# univ_3-2-3-x-rev2.net
KiCad netlist of a schematic drawn in EAGLE
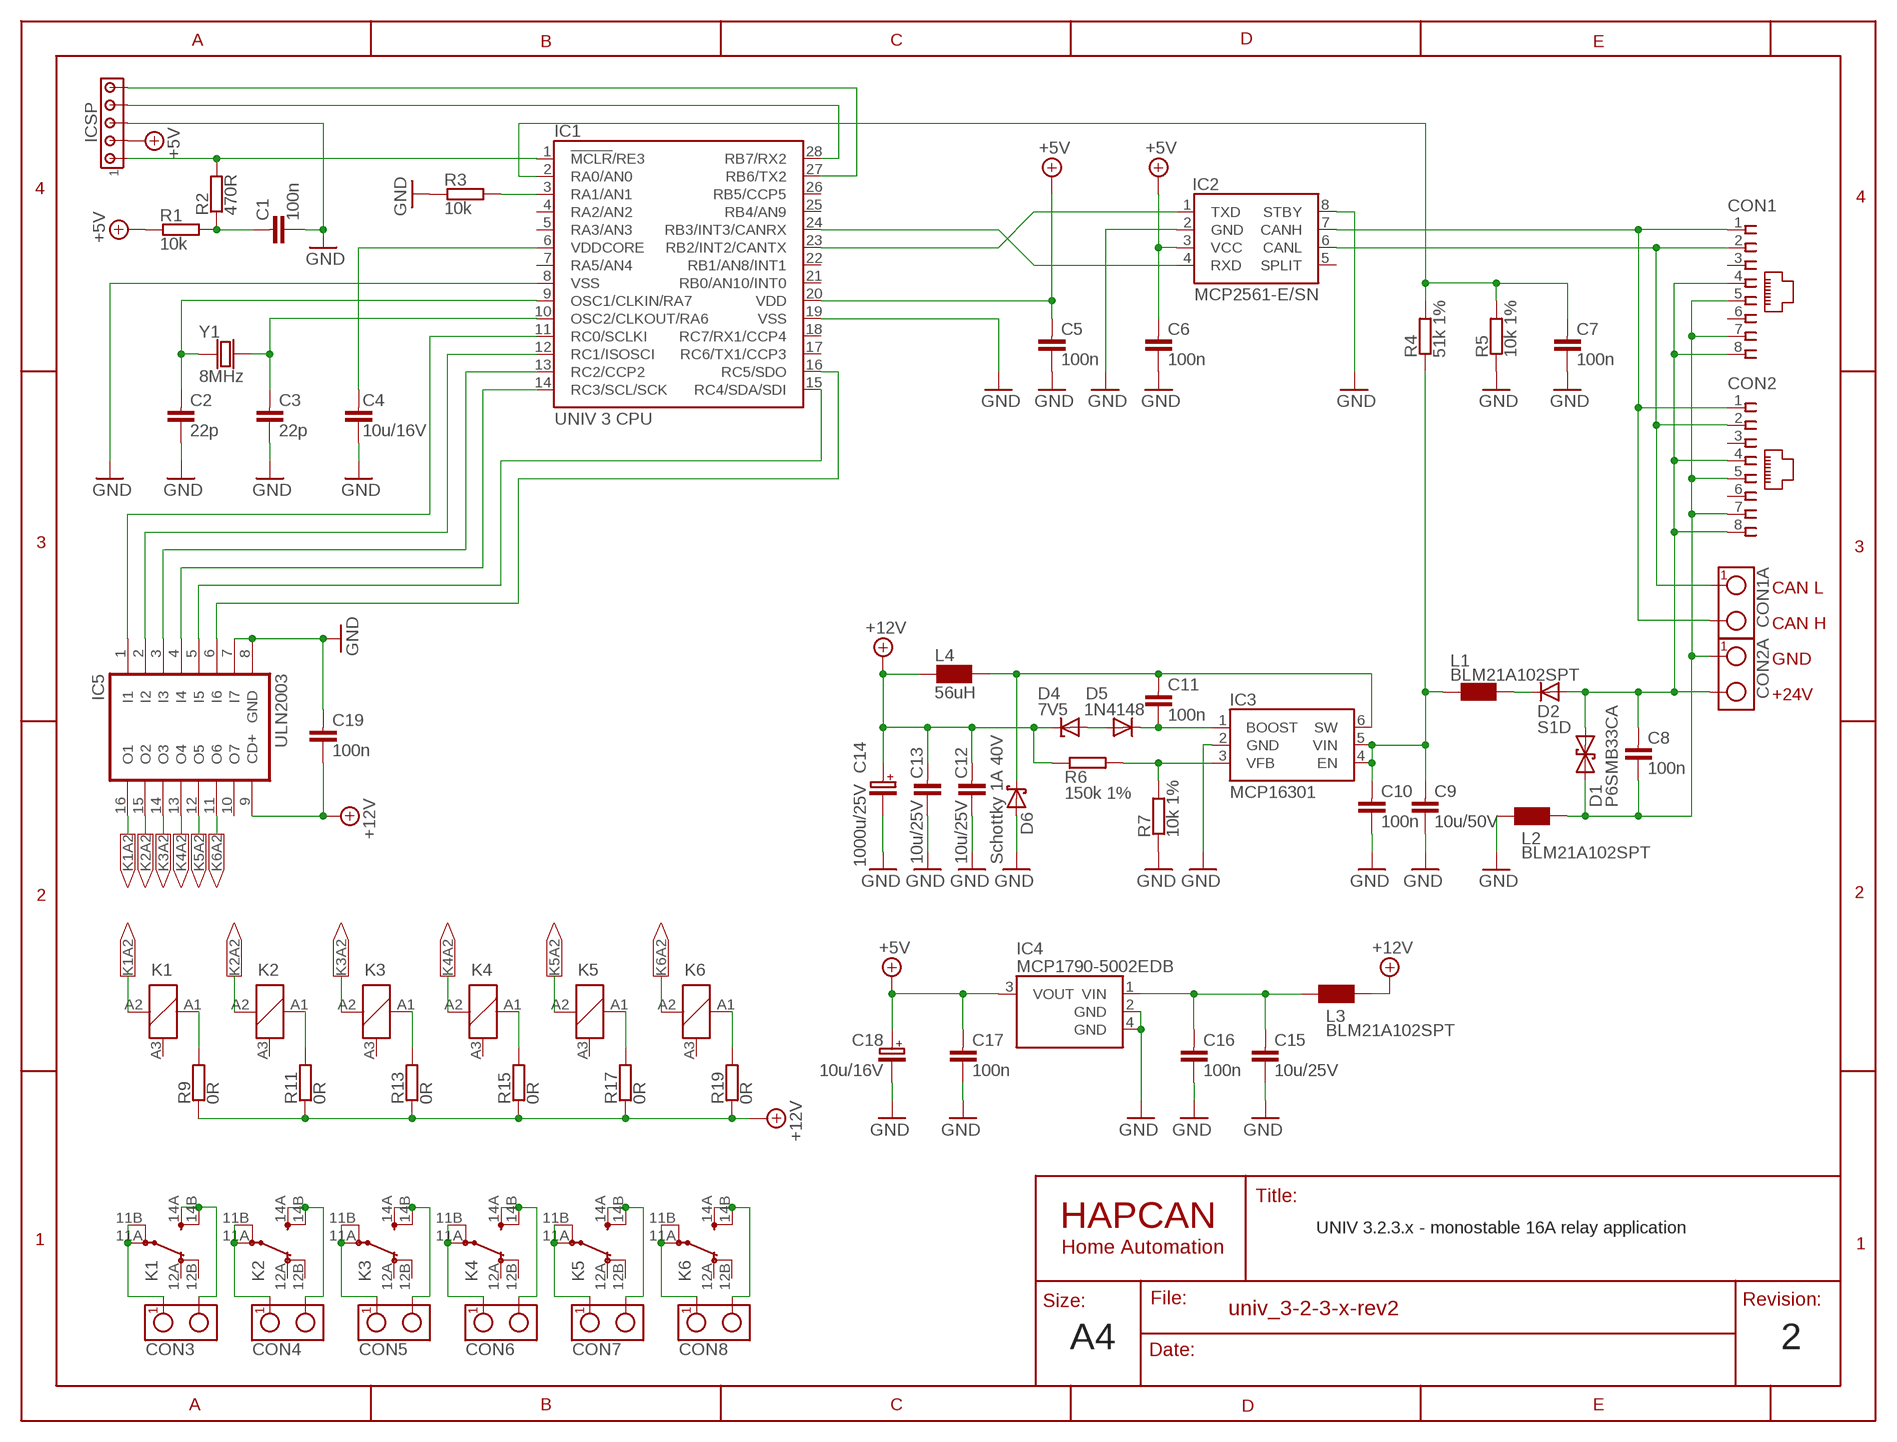
[diagram p0: schematic, sheet 1]

(export (version "E")
  (design (tool "Eeschema 10.0.6"))
  (components
    (comp (ref "C1")
      (value "100n")
      (footprint "eagle-import:0805")
      (libsource (lib "eagle-import") (part "CAPACITOR0805"))
    )
    (comp (ref "C2")
      (value "22p")
      (footprint "eagle-import:0805")
      (libsource (lib "eagle-import") (part "CAPACITOR0805"))
    )
    (comp (ref "C3")
      (value "22p")
      (footprint "eagle-import:0805")
      (libsource (lib "eagle-import") (part "CAPACITOR0805"))
    )
    (comp (ref "C4")
      (value "10u/16V")
      (footprint "eagle-import:0805")
      (libsource (lib "eagle-import") (part "CAPACITOR0805"))
    )
    (comp (ref "C5")
      (value "100n")
      (footprint "eagle-import:0805")
      (libsource (lib "eagle-import") (part "CAPACITOR0805"))
    )
    (comp (ref "C6")
      (value "100n")
      (footprint "eagle-import:0805")
      (libsource (lib "eagle-import") (part "CAPACITOR0805"))
    )
    (comp (ref "C7")
      (value "100n")
      (footprint "eagle-import:0805")
      (libsource (lib "eagle-import") (part "CAPACITOR0805"))
    )
    (comp (ref "C8")
      (value "100n")
      (footprint "eagle-import:0805")
      (libsource (lib "eagle-import") (part "CAPACITOR0805"))
    )
    (comp (ref "C9")
      (value "10u/50V")
      (footprint "eagle-import:1210")
      (libsource (lib "eagle-import") (part "CAPACITOR1210"))
    )
    (comp (ref "C10")
      (value "100n")
      (footprint "eagle-import:0805")
      (libsource (lib "eagle-import") (part "CAPACITOR0805"))
    )
    (comp (ref "C11")
      (value "100n")
      (footprint "eagle-import:0805")
      (libsource (lib "eagle-import") (part "CAPACITOR0805"))
    )
    (comp (ref "C12")
      (value "10u/25V")
      (footprint "eagle-import:1206")
      (libsource (lib "eagle-import") (part "CAPACITOR1206"))
    )
    (comp (ref "C13")
      (value "10u/25V")
      (footprint "eagle-import:1206")
      (libsource (lib "eagle-import") (part "CAPACITOR1206"))
    )
    (comp (ref "C14")
      (value "1000u/25V")
      (footprint "eagle-import:CAP-5X10.5")
      (libsource (lib "eagle-import") (part "CAPACITOR-POLARIZED-5X10.5"))
    )
    (comp (ref "C15")
      (value "10u/25V")
      (footprint "eagle-import:1206")
      (libsource (lib "eagle-import") (part "CAPACITOR1206"))
    )
    (comp (ref "C16")
      (value "100n")
      (footprint "eagle-import:0805")
      (libsource (lib "eagle-import") (part "CAPACITOR0805"))
    )
    (comp (ref "C17")
      (value "100n")
      (footprint "eagle-import:0805")
      (libsource (lib "eagle-import") (part "CAPACITOR0805"))
    )
    (comp (ref "C18")
      (value "10u/16V")
      (footprint "eagle-import:SMC_B")
      (libsource (lib "eagle-import") (part "CAPACITOR-POLARIZED-SMC_B"))
    )
    (comp (ref "C19")
      (value "100n")
      (footprint "eagle-import:0805")
      (libsource (lib "eagle-import") (part "CAPACITOR0805"))
    )
    (comp (ref "CON1")
      (value "RJ45-SOCKET")
      (footprint "eagle-import:RJ45-PCB-SOCKET")
      (libsource (lib "eagle-import") (part "RJ45-SOCKET"))
    )
    (comp (ref "CON1A")
      (value "TERMINAL-2")
      (footprint "eagle-import:ARK2-5X10,5MM")
      (libsource (lib "eagle-import") (part "TERMINAL-2-5X10,5MM"))
    )
    (comp (ref "CON2")
      (value "RJ45-SOCKET")
      (footprint "eagle-import:RJ45-PCB-SOCKET")
      (libsource (lib "eagle-import") (part "RJ45-SOCKET"))
    )
    (comp (ref "CON2A")
      (value "TERMINAL-2")
      (footprint "eagle-import:ARK2-5X10,5MM")
      (libsource (lib "eagle-import") (part "TERMINAL-2-5X10,5MM"))
    )
    (comp (ref "CON3")
      (value "TERMINAL-2")
      (footprint "eagle-import:ARK2-7.5X10.5MM")
      (libsource (lib "eagle-import") (part "TERMINAL-2-7.5X10.5MM"))
    )
    (comp (ref "CON4")
      (value "TERMINAL-2")
      (footprint "eagle-import:ARK2-7.5X10.5MM")
      (libsource (lib "eagle-import") (part "TERMINAL-2-7.5X10.5MM"))
    )
    (comp (ref "CON5")
      (value "TERMINAL-2")
      (footprint "eagle-import:ARK2-7.5X10.5MM")
      (libsource (lib "eagle-import") (part "TERMINAL-2-7.5X10.5MM"))
    )
    (comp (ref "CON6")
      (value "TERMINAL-2")
      (footprint "eagle-import:ARK2-7.5X10.5MM")
      (libsource (lib "eagle-import") (part "TERMINAL-2-7.5X10.5MM"))
    )
    (comp (ref "CON7")
      (value "TERMINAL-2")
      (footprint "eagle-import:ARK2-7.5X10.5MM")
      (libsource (lib "eagle-import") (part "TERMINAL-2-7.5X10.5MM"))
    )
    (comp (ref "CON8")
      (value "TERMINAL-2")
      (footprint "eagle-import:ARK2-7.5X10.5MM")
      (libsource (lib "eagle-import") (part "TERMINAL-2-7.5X10.5MM"))
    )
    (comp (ref "D1")
      (value "P6SMB33CA")
      (footprint "eagle-import:DO-214_TRANSIL2")
      (libsource (lib "eagle-import") (part "DIODE_TRANSIL2"))
    )
    (comp (ref "D2")
      (value "S1D")
      (footprint "eagle-import:DO-214")
      (libsource (lib "eagle-import") (part "DIODE_DO-214"))
    )
    (comp (ref "D4")
      (value "7V5")
      (footprint "eagle-import:SOD-80")
      (libsource (lib "eagle-import") (part "DIODE_ZENER_SOD-80"))
    )
    (comp (ref "D5")
      (value "1N4148")
      (footprint "eagle-import:0805")
      (libsource (lib "eagle-import") (part "DIODE_0805"))
    )
    (comp (ref "D6")
      (value "Schottky 1A 40V")
      (footprint "eagle-import:DO-214")
      (libsource (lib "eagle-import") (part "DIODE_TRANSIL1_DO214"))
    )
    (comp (ref "IC1")
      (value "UNIV 3 CPU")
      (footprint "eagle-import:UNIV3CPU")
      (libsource (lib "eagle-import") (part "UNIV3CPU-I/SO"))
    )
    (comp (ref "IC2")
      (value "MCP2561-E/SN")
      (footprint "eagle-import:SO-08")
      (libsource (lib "eagle-import") (part "MCP2561-E/SN"))
    )
    (comp (ref "IC3")
      (value "MCP16301")
      (footprint "eagle-import:SOT-23-6")
      (libsource (lib "eagle-import") (part "MCP16301SOT23-6"))
    )
    (comp (ref "IC4")
      (value "MCP1790-5002EDB")
      (footprint "eagle-import:SOT-223")
      (libsource (lib "eagle-import") (part "MCP1826SOT223-3"))
    )
    (comp (ref "IC5")
      (value "ULN2003")
      (footprint "eagle-import:SO-16")
      (libsource (lib "eagle-import") (part "ULN2003"))
    )
    (comp (ref "ICSP")
      (value "HEADER5")
      (footprint "eagle-import:SIP-5")
      (libsource (lib "eagle-import") (part "HEADER5"))
    )
    (comp (ref "K1")
      (value "RELAY_RT")
      (footprint "eagle-import:RELAY_RT")
      (libsource (lib "eagle-import") (part "RELAY_RT"))
    )
    (comp (ref "K2")
      (value "RELAY_RT")
      (footprint "eagle-import:RELAY_RT")
      (libsource (lib "eagle-import") (part "RELAY_RT"))
    )
    (comp (ref "K3")
      (value "RELAY_RT")
      (footprint "eagle-import:RELAY_RT")
      (libsource (lib "eagle-import") (part "RELAY_RT"))
    )
    (comp (ref "K4")
      (value "RELAY_RT")
      (footprint "eagle-import:RELAY_RT")
      (libsource (lib "eagle-import") (part "RELAY_RT"))
    )
    (comp (ref "K5")
      (value "RELAY_RT")
      (footprint "eagle-import:RELAY_RT")
      (libsource (lib "eagle-import") (part "RELAY_RT"))
    )
    (comp (ref "K6")
      (value "RELAY_RT")
      (footprint "eagle-import:RELAY_RT")
      (libsource (lib "eagle-import") (part "RELAY_RT"))
    )
    (comp (ref "L1")
      (value "BLM21A102SPT")
      (footprint "eagle-import:0805")
      (libsource (lib "eagle-import") (part "CHOKE0805"))
    )
    (comp (ref "L2")
      (value "BLM21A102SPT")
      (footprint "eagle-import:0805")
      (libsource (lib "eagle-import") (part "CHOKE0805"))
    )
    (comp (ref "L3")
      (value "BLM21A102SPT")
      (footprint "eagle-import:0805")
      (libsource (lib "eagle-import") (part "CHOKE0805"))
    )
    (comp (ref "L4")
      (value "56uH")
      (footprint "eagle-import:CHOKE-DER0705")
      (libsource (lib "eagle-import") (part "CHOKEDER0705"))
    )
    (comp (ref "R1")
      (value "10k")
      (footprint "eagle-import:0805")
      (libsource (lib "eagle-import") (part "RESISTOR0805"))
    )
    (comp (ref "R2")
      (value "470R")
      (footprint "eagle-import:0805")
      (libsource (lib "eagle-import") (part "RESISTOR0805"))
    )
    (comp (ref "R3")
      (value "10k")
      (footprint "eagle-import:0805")
      (libsource (lib "eagle-import") (part "RESISTOR0805"))
    )
    (comp (ref "R4")
      (value "51k 1%")
      (footprint "eagle-import:0805")
      (libsource (lib "eagle-import") (part "RESISTOR0805"))
    )
    (comp (ref "R5")
      (value "10k 1%")
      (footprint "eagle-import:0805")
      (libsource (lib "eagle-import") (part "RESISTOR0805"))
    )
    (comp (ref "R6")
      (value "150k 1%")
      (footprint "eagle-import:0805")
      (libsource (lib "eagle-import") (part "RESISTOR0805"))
    )
    (comp (ref "R7")
      (value "10k 1%")
      (footprint "eagle-import:0805")
      (libsource (lib "eagle-import") (part "RESISTOR0805"))
    )
    (comp (ref "R9")
      (value "0R")
      (footprint "eagle-import:1206")
      (libsource (lib "eagle-import") (part "RESISTOR1206"))
    )
    (comp (ref "R11")
      (value "0R")
      (footprint "eagle-import:1206")
      (libsource (lib "eagle-import") (part "RESISTOR1206"))
    )
    (comp (ref "R13")
      (value "0R")
      (footprint "eagle-import:1206")
      (libsource (lib "eagle-import") (part "RESISTOR1206"))
    )
    (comp (ref "R15")
      (value "0R")
      (footprint "eagle-import:1206")
      (libsource (lib "eagle-import") (part "RESISTOR1206"))
    )
    (comp (ref "R17")
      (value "0R")
      (footprint "eagle-import:1206")
      (libsource (lib "eagle-import") (part "RESISTOR1206"))
    )
    (comp (ref "R19")
      (value "0R")
      (footprint "eagle-import:1206")
      (libsource (lib "eagle-import") (part "RESISTOR1206"))
    )
    (comp (ref "Y1")
      (value "8MHz")
      (footprint "eagle-import:CRYSTAL-HC49V")
      (libsource (lib "eagle-import") (part "CRYSTAL-HC49V"))
    )
  )
  (nets
    (net (code "1") (name "+5V") (class "Default")
      (node (ref "C17") (pin "1") (pinfunction "1_1") (pintype "passive"))
      (node (ref "C18") (pin "+") (pinfunction "1_+") (pintype "passive"))
      (node (ref "C5") (pin "1") (pinfunction "1_1") (pintype "passive"))
      (node (ref "C6") (pin "1") (pinfunction "1_1") (pintype "passive"))
      (node (ref "IC1") (pin "20") (pinfunction "VDD_20") (pintype "bidirectional"))
      (node (ref "IC2") (pin "3") (pinfunction "VCC_3") (pintype "bidirectional"))
      (node (ref "IC4") (pin "3") (pinfunction "VOUT_3") (pintype "bidirectional"))
      (node (ref "ICSP") (pin "2") (pinfunction "2_2") (pintype "passive"))
      (node (ref "R1") (pin "1") (pinfunction "1_1") (pintype "passive"))
    )
    (net (code "2") (name "+12V") (class "Default")
      (node (ref "C12") (pin "1") (pinfunction "1_1") (pintype "passive"))
      (node (ref "C13") (pin "1") (pinfunction "1_1") (pintype "passive"))
      (node (ref "C14") (pin "+") (pinfunction "1_+") (pintype "passive"))
      (node (ref "C19") (pin "2") (pinfunction "2_2") (pintype "passive"))
      (node (ref "D4") (pin "C") (pinfunction "C_C") (pintype "passive"))
      (node (ref "IC5") (pin "9") (pinfunction "CD+_9") (pintype "passive"))
      (node (ref "L3") (pin "2") (pinfunction "2_2") (pintype "passive"))
      (node (ref "L4") (pin "1") (pinfunction "1_1") (pintype "passive"))
      (node (ref "R11") (pin "1") (pinfunction "1_1") (pintype "passive"))
      (node (ref "R13") (pin "1") (pinfunction "1_1") (pintype "passive"))
      (node (ref "R15") (pin "1") (pinfunction "1_1") (pintype "passive"))
      (node (ref "R17") (pin "1") (pinfunction "1_1") (pintype "passive"))
      (node (ref "R19") (pin "1") (pinfunction "1_1") (pintype "passive"))
      (node (ref "R6") (pin "1") (pinfunction "1_1") (pintype "passive"))
      (node (ref "R9") (pin "1") (pinfunction "1_1") (pintype "passive"))
    )
    (net (code "3") (name "/K1A2") (class "Default")
      (node (ref "IC5") (pin "16") (pinfunction "O1_16") (pintype "open_collector"))
      (node (ref "K1") (pin "A2") (pinfunction "R+_A2") (pintype "passive"))
    )
    (net (code "4") (name "/K2A2") (class "Default")
      (node (ref "IC5") (pin "15") (pinfunction "O2_15") (pintype "open_collector"))
      (node (ref "K2") (pin "A2") (pinfunction "R+_A2") (pintype "passive"))
    )
    (net (code "5") (name "/K3A2") (class "Default")
      (node (ref "IC5") (pin "14") (pinfunction "O3_14") (pintype "open_collector"))
      (node (ref "K3") (pin "A2") (pinfunction "R+_A2") (pintype "passive"))
    )
    (net (code "6") (name "/K4A2") (class "Default")
      (node (ref "IC5") (pin "13") (pinfunction "O4_13") (pintype "open_collector"))
      (node (ref "K4") (pin "A2") (pinfunction "R+_A2") (pintype "passive"))
    )
    (net (code "7") (name "/K5A2") (class "Default")
      (node (ref "IC5") (pin "12") (pinfunction "O5_12") (pintype "open_collector"))
      (node (ref "K5") (pin "A2") (pinfunction "R+_A2") (pintype "passive"))
    )
    (net (code "8") (name "/K6A2") (class "Default")
      (node (ref "IC5") (pin "11") (pinfunction "O6_11") (pintype "open_collector"))
      (node (ref "K6") (pin "A2") (pinfunction "R+_A2") (pintype "passive"))
    )
    (net (code "9") (name "GND") (class "Default")
      (node (ref "C1") (pin "2") (pinfunction "2_2") (pintype "passive"))
      (node (ref "C10") (pin "2") (pinfunction "2_2") (pintype "passive"))
      (node (ref "C12") (pin "2") (pinfunction "2_2") (pintype "passive"))
      (node (ref "C13") (pin "2") (pinfunction "2_2") (pintype "passive"))
      (node (ref "C14") (pin "-") (pinfunction "2_-") (pintype "passive"))
      (node (ref "C15") (pin "2") (pinfunction "2_2") (pintype "passive"))
      (node (ref "C16") (pin "2") (pinfunction "2_2") (pintype "passive"))
      (node (ref "C17") (pin "2") (pinfunction "2_2") (pintype "passive"))
      (node (ref "C18") (pin "-") (pinfunction "2_-") (pintype "passive"))
      (node (ref "C19") (pin "1") (pinfunction "1_1") (pintype "passive"))
      (node (ref "C2") (pin "2") (pinfunction "2_2") (pintype "passive"))
      (node (ref "C3") (pin "2") (pinfunction "2_2") (pintype "passive"))
      (node (ref "C4") (pin "2") (pinfunction "2_2") (pintype "passive"))
      (node (ref "C5") (pin "2") (pinfunction "2_2") (pintype "passive"))
      (node (ref "C6") (pin "2") (pinfunction "2_2") (pintype "passive"))
      (node (ref "C7") (pin "2") (pinfunction "2_2") (pintype "passive"))
      (node (ref "C9") (pin "2") (pinfunction "2_2") (pintype "passive"))
      (node (ref "D6") (pin "A") (pinfunction "A_A") (pintype "passive"))
      (node (ref "IC1") (pin "19") (pinfunction "VSS_19") (pintype "bidirectional"))
      (node (ref "IC1") (pin "8") (pinfunction "VSS_8") (pintype "bidirectional"))
      (node (ref "IC2") (pin "2") (pinfunction "GND_2") (pintype "bidirectional"))
      (node (ref "IC2") (pin "8") (pinfunction "STBY_8") (pintype "bidirectional"))
      (node (ref "IC3") (pin "2") (pinfunction "GND_2") (pintype "bidirectional"))
      (node (ref "IC4") (pin "2") (pinfunction "GND_2") (pintype "bidirectional"))
      (node (ref "IC4") (pin "4") (pinfunction "GND_4") (pintype "bidirectional"))
      (node (ref "IC5") (pin "7") (pinfunction "I7_7") (pintype "input"))
      (node (ref "IC5") (pin "8") (pinfunction "GND_8") (pintype "power_in"))
      (node (ref "ICSP") (pin "3") (pinfunction "3_3") (pintype "passive"))
      (node (ref "L2") (pin "1") (pinfunction "1_1") (pintype "passive"))
      (node (ref "R3") (pin "1") (pinfunction "1_1") (pintype "passive"))
      (node (ref "R5") (pin "1") (pinfunction "1_1") (pintype "passive"))
      (node (ref "R7") (pin "1") (pinfunction "1_1") (pintype "passive"))
    )
    (net (code "10") (name "Net-(C1-Pad1)") (class "Default")
      (node (ref "C1") (pin "1") (pinfunction "1_1") (pintype "passive"))
      (node (ref "R1") (pin "2") (pinfunction "2_2") (pintype "passive"))
      (node (ref "R2") (pin "1") (pinfunction "1_1") (pintype "passive"))
    )
    (net (code "11") (name "Net-(D1-1)") (class "Default")
      (node (ref "C8") (pin "2") (pinfunction "2_2") (pintype "passive"))
      (node (ref "CON1") (pin "5") (pinfunction "5_5") (pintype "passive"))
      (node (ref "CON1") (pin "7") (pinfunction "7_7") (pintype "passive"))
      (node (ref "CON2") (pin "5") (pinfunction "5_5") (pintype "passive"))
      (node (ref "CON2") (pin "7") (pinfunction "7_7") (pintype "passive"))
      (node (ref "CON2A") (pin "1") (pinfunction "1_1") (pintype "passive"))
      (node (ref "D1") (pin "A") (pinfunction "1_A") (pintype "passive"))
      (node (ref "L2") (pin "2") (pinfunction "2_2") (pintype "passive"))
    )
    (net (code "12") (name "Net-(D1-2)") (class "Default")
      (node (ref "C8") (pin "1") (pinfunction "1_1") (pintype "passive"))
      (node (ref "CON1") (pin "4") (pinfunction "4_4") (pintype "passive"))
      (node (ref "CON1") (pin "8") (pinfunction "8_8") (pintype "passive"))
      (node (ref "CON2") (pin "4") (pinfunction "4_4") (pintype "passive"))
      (node (ref "CON2") (pin "8") (pinfunction "8_8") (pintype "passive"))
      (node (ref "CON2A") (pin "2") (pinfunction "2_2") (pintype "passive"))
      (node (ref "D1") (pin "C") (pinfunction "2_C") (pintype "passive"))
      (node (ref "D2") (pin "A") (pinfunction "A_A") (pintype "passive"))
    )
    (net (code "13") (name "Net-(D2-PadC)") (class "Default")
      (node (ref "D2") (pin "C") (pinfunction "C_C") (pintype "passive"))
      (node (ref "L1") (pin "2") (pinfunction "2_2") (pintype "passive"))
    )
    (net (code "14") (name "Net-(D5-A)") (class "Default")
      (node (ref "D4") (pin "A") (pinfunction "A_A") (pintype "passive"))
      (node (ref "D5") (pin "2") (pinfunction "A_2") (pintype "passive"))
    )
    (net (code "15") (name "Net-(D5-C)") (class "Default")
      (node (ref "C11") (pin "2") (pinfunction "2_2") (pintype "passive"))
      (node (ref "D5") (pin "1") (pinfunction "C_1") (pintype "passive"))
      (node (ref "IC3") (pin "1") (pinfunction "BOOST_1") (pintype "bidirectional"))
    )
    (net (code "16") (name "Net-(IC1-OSC1{slash}CLKIN{slash}RA7)") (class "Default")
      (node (ref "C2") (pin "1") (pinfunction "1_1") (pintype "passive"))
      (node (ref "IC1") (pin "9") (pinfunction "OSC1/CLKIN/RA7_9") (pintype "bidirectional"))
      (node (ref "Y1") (pin "1") (pinfunction "1_1") (pintype "passive"))
    )
    (net (code "17") (name "Net-(IC1-OSC2{slash}CLKOUT{slash}RA6)") (class "Default")
      (node (ref "C3") (pin "1") (pinfunction "1_1") (pintype "passive"))
      (node (ref "IC1") (pin "10") (pinfunction "OSC2/CLKOUT/RA6_10") (pintype "bidirectional"))
      (node (ref "Y1") (pin "2") (pinfunction "2_2") (pintype "passive"))
    )
    (net (code "18") (name "Net-(IC1-RA0{slash}AN0)") (class "Default")
      (node (ref "C7") (pin "1") (pinfunction "1_1") (pintype "passive"))
      (node (ref "IC1") (pin "2") (pinfunction "RA0/AN0_2") (pintype "bidirectional"))
      (node (ref "R4") (pin "2") (pinfunction "2_2") (pintype "passive"))
      (node (ref "R5") (pin "2") (pinfunction "2_2") (pintype "passive"))
    )
    (net (code "19") (name "Net-(IC1-RA1{slash}AN1)") (class "Default")
      (node (ref "IC1") (pin "3") (pinfunction "RA1/AN1_3") (pintype "bidirectional"))
      (node (ref "R3") (pin "2") (pinfunction "2_2") (pintype "passive"))
    )
    (net (code "20") (name "Net-(IC1-RB2{slash}INT2{slash}CANTX)") (class "Default")
      (node (ref "IC1") (pin "23") (pinfunction "RB2/INT2/CANTX_23") (pintype "bidirectional"))
      (node (ref "IC2") (pin "1") (pinfunction "TXD_1") (pintype "bidirectional"))
    )
    (net (code "21") (name "Net-(IC1-RB3{slash}INT3{slash}CANRX)") (class "Default")
      (node (ref "IC1") (pin "24") (pinfunction "RB3/INT3/CANRX_24") (pintype "bidirectional"))
      (node (ref "IC2") (pin "4") (pinfunction "RXD_4") (pintype "bidirectional"))
    )
    (net (code "22") (name "Net-(IC1-RB6{slash}TX2)") (class "Default")
      (node (ref "IC1") (pin "27") (pinfunction "RB6/TX2_27") (pintype "bidirectional"))
      (node (ref "ICSP") (pin "5") (pinfunction "5_5") (pintype "passive"))
    )
    (net (code "23") (name "Net-(IC1-RB7{slash}RX2)") (class "Default")
      (node (ref "IC1") (pin "28") (pinfunction "RB7/RX2_28") (pintype "bidirectional"))
      (node (ref "ICSP") (pin "4") (pinfunction "4_4") (pintype "passive"))
    )
    (net (code "24") (name "Net-(IC1-RC0{slash}SCLKI)") (class "Default")
      (node (ref "IC1") (pin "11") (pinfunction "RC0/SCLKI_11") (pintype "bidirectional"))
      (node (ref "IC5") (pin "1") (pinfunction "I1_1") (pintype "input"))
    )
    (net (code "25") (name "Net-(IC1-RC1{slash}ISOSCI)") (class "Default")
      (node (ref "IC1") (pin "12") (pinfunction "RC1/ISOSCI_12") (pintype "bidirectional"))
      (node (ref "IC5") (pin "2") (pinfunction "I2_2") (pintype "input"))
    )
    (net (code "26") (name "Net-(IC1-RC2{slash}CCP2)") (class "Default")
      (node (ref "IC1") (pin "13") (pinfunction "RC2/CCP2_13") (pintype "bidirectional"))
      (node (ref "IC5") (pin "3") (pinfunction "I3_3") (pintype "input"))
    )
    (net (code "27") (name "Net-(IC1-RC3{slash}SCL{slash}SCK)") (class "Default")
      (node (ref "IC1") (pin "14") (pinfunction "RC3/SCL/SCK_14") (pintype "bidirectional"))
      (node (ref "IC5") (pin "4") (pinfunction "I4_4") (pintype "input"))
    )
    (net (code "28") (name "Net-(IC1-RC4{slash}SDA{slash}SDI)") (class "Default")
      (node (ref "IC1") (pin "15") (pinfunction "RC4/SDA/SDI_15") (pintype "bidirectional"))
      (node (ref "IC5") (pin "5") (pinfunction "I5_5") (pintype "input"))
    )
    (net (code "29") (name "Net-(IC1-RC5{slash}SDO)") (class "Default")
      (node (ref "IC1") (pin "16") (pinfunction "RC5/SDO_16") (pintype "bidirectional"))
      (node (ref "IC5") (pin "6") (pinfunction "I6_6") (pintype "input"))
    )
    (net (code "30") (name "Net-(IC1-VDDCORE)") (class "Default")
      (node (ref "C4") (pin "1") (pinfunction "1_1") (pintype "passive"))
      (node (ref "IC1") (pin "6") (pinfunction "VDDCORE_6") (pintype "bidirectional"))
    )
    (net (code "31") (name "Net-(IC1-~{MCLR}{slash}RE3)") (class "Default")
      (node (ref "IC1") (pin "1") (pinfunction "~{MCLR}/RE3_1") (pintype "bidirectional"))
      (node (ref "ICSP") (pin "1") (pinfunction "1_1") (pintype "passive"))
      (node (ref "R2") (pin "2") (pinfunction "2_2") (pintype "passive"))
    )
    (net (code "32") (name "Net-(IC2-CANH)") (class "Default")
      (node (ref "CON1") (pin "1") (pinfunction "1_1") (pintype "passive"))
      (node (ref "CON1A") (pin "2") (pinfunction "2_2") (pintype "passive"))
      (node (ref "CON2") (pin "1") (pinfunction "1_1") (pintype "passive"))
      (node (ref "IC2") (pin "7") (pinfunction "CANH_7") (pintype "bidirectional"))
    )
    (net (code "33") (name "Net-(IC2-CANL)") (class "Default")
      (node (ref "CON1") (pin "2") (pinfunction "2_2") (pintype "passive"))
      (node (ref "CON1A") (pin "1") (pinfunction "1_1") (pintype "passive"))
      (node (ref "CON2") (pin "2") (pinfunction "2_2") (pintype "passive"))
      (node (ref "IC2") (pin "6") (pinfunction "CANL_6") (pintype "bidirectional"))
    )
    (net (code "34") (name "Net-(IC3-EN)") (class "Default")
      (node (ref "C10") (pin "1") (pinfunction "1_1") (pintype "passive"))
      (node (ref "C9") (pin "1") (pinfunction "1_1") (pintype "passive"))
      (node (ref "IC3") (pin "4") (pinfunction "EN_4") (pintype "bidirectional"))
      (node (ref "IC3") (pin "5") (pinfunction "VIN_5") (pintype "bidirectional"))
      (node (ref "L1") (pin "1") (pinfunction "1_1") (pintype "passive"))
      (node (ref "R4") (pin "1") (pinfunction "1_1") (pintype "passive"))
    )
    (net (code "35") (name "Net-(IC3-SW)") (class "Default")
      (node (ref "C11") (pin "1") (pinfunction "1_1") (pintype "passive"))
      (node (ref "D6") (pin "C") (pinfunction "C_C") (pintype "passive"))
      (node (ref "IC3") (pin "6") (pinfunction "SW_6") (pintype "bidirectional"))
      (node (ref "L4") (pin "2") (pinfunction "2_2") (pintype "passive"))
    )
    (net (code "36") (name "Net-(IC3-VFB)") (class "Default")
      (node (ref "IC3") (pin "3") (pinfunction "VFB_3") (pintype "bidirectional"))
      (node (ref "R6") (pin "2") (pinfunction "2_2") (pintype "passive"))
      (node (ref "R7") (pin "2") (pinfunction "2_2") (pintype "passive"))
    )
    (net (code "37") (name "Net-(IC4-VIN)") (class "Default")
      (node (ref "C15") (pin "1") (pinfunction "1_1") (pintype "passive"))
      (node (ref "C16") (pin "1") (pinfunction "1_1") (pintype "passive"))
      (node (ref "IC4") (pin "1") (pinfunction "VIN_1") (pintype "bidirectional"))
      (node (ref "L3") (pin "1") (pinfunction "1_1") (pintype "passive"))
    )
    (net (code "38") (name "Net-(K1A-PA)") (class "Default")
      (node (ref "CON3") (pin "1") (pinfunction "1_1") (pintype "passive"))
      (node (ref "K1") (pin "11A") (pinfunction "PA_11A") (pintype "passive"))
      (node (ref "K1") (pin "11B") (pinfunction "PB_11B") (pintype "passive"))
    )
    (net (code "39") (name "Net-(K1A-SA)") (class "Default")
      (node (ref "CON3") (pin "2") (pinfunction "2_2") (pintype "passive"))
      (node (ref "K1") (pin "14A") (pinfunction "SA_14A") (pintype "passive"))
      (node (ref "K1") (pin "14B") (pinfunction "SB_14B") (pintype "passive"))
    )
    (net (code "40") (name "Net-(K1B-S+)") (class "Default")
      (node (ref "K1") (pin "A1") (pinfunction "S+_A1") (pintype "passive"))
      (node (ref "R9") (pin "2") (pinfunction "2_2") (pintype "passive"))
    )
    (net (code "41") (name "Net-(K2A-PA)") (class "Default")
      (node (ref "CON4") (pin "1") (pinfunction "1_1") (pintype "passive"))
      (node (ref "K2") (pin "11A") (pinfunction "PA_11A") (pintype "passive"))
      (node (ref "K2") (pin "11B") (pinfunction "PB_11B") (pintype "passive"))
    )
    (net (code "42") (name "Net-(K2A-SA)") (class "Default")
      (node (ref "CON4") (pin "2") (pinfunction "2_2") (pintype "passive"))
      (node (ref "K2") (pin "14A") (pinfunction "SA_14A") (pintype "passive"))
      (node (ref "K2") (pin "14B") (pinfunction "SB_14B") (pintype "passive"))
    )
    (net (code "43") (name "Net-(K2B-S+)") (class "Default")
      (node (ref "K2") (pin "A1") (pinfunction "S+_A1") (pintype "passive"))
      (node (ref "R11") (pin "2") (pinfunction "2_2") (pintype "passive"))
    )
    (net (code "44") (name "Net-(K3A-PA)") (class "Default")
      (node (ref "CON5") (pin "1") (pinfunction "1_1") (pintype "passive"))
      (node (ref "K3") (pin "11A") (pinfunction "PA_11A") (pintype "passive"))
      (node (ref "K3") (pin "11B") (pinfunction "PB_11B") (pintype "passive"))
    )
    (net (code "45") (name "Net-(K3A-SA)") (class "Default")
      (node (ref "CON5") (pin "2") (pinfunction "2_2") (pintype "passive"))
      (node (ref "K3") (pin "14A") (pinfunction "SA_14A") (pintype "passive"))
      (node (ref "K3") (pin "14B") (pinfunction "SB_14B") (pintype "passive"))
    )
    (net (code "46") (name "Net-(K3B-S+)") (class "Default")
      (node (ref "K3") (pin "A1") (pinfunction "S+_A1") (pintype "passive"))
      (node (ref "R13") (pin "2") (pinfunction "2_2") (pintype "passive"))
    )
    (net (code "47") (name "Net-(K4A-PA)") (class "Default")
      (node (ref "CON6") (pin "1") (pinfunction "1_1") (pintype "passive"))
      (node (ref "K4") (pin "11A") (pinfunction "PA_11A") (pintype "passive"))
      (node (ref "K4") (pin "11B") (pinfunction "PB_11B") (pintype "passive"))
    )
    (net (code "48") (name "Net-(K4A-SA)") (class "Default")
      (node (ref "CON6") (pin "2") (pinfunction "2_2") (pintype "passive"))
      (node (ref "K4") (pin "14A") (pinfunction "SA_14A") (pintype "passive"))
      (node (ref "K4") (pin "14B") (pinfunction "SB_14B") (pintype "passive"))
    )
    (net (code "49") (name "Net-(K4B-S+)") (class "Default")
      (node (ref "K4") (pin "A1") (pinfunction "S+_A1") (pintype "passive"))
      (node (ref "R15") (pin "2") (pinfunction "2_2") (pintype "passive"))
    )
    (net (code "50") (name "Net-(K5A-PA)") (class "Default")
      (node (ref "CON7") (pin "1") (pinfunction "1_1") (pintype "passive"))
      (node (ref "K5") (pin "11A") (pinfunction "PA_11A") (pintype "passive"))
      (node (ref "K5") (pin "11B") (pinfunction "PB_11B") (pintype "passive"))
    )
    (net (code "51") (name "Net-(K5A-SA)") (class "Default")
      (node (ref "CON7") (pin "2") (pinfunction "2_2") (pintype "passive"))
      (node (ref "K5") (pin "14A") (pinfunction "SA_14A") (pintype "passive"))
      (node (ref "K5") (pin "14B") (pinfunction "SB_14B") (pintype "passive"))
    )
    (net (code "52") (name "Net-(K5B-S+)") (class "Default")
      (node (ref "K5") (pin "A1") (pinfunction "S+_A1") (pintype "passive"))
      (node (ref "R17") (pin "2") (pinfunction "2_2") (pintype "passive"))
    )
    (net (code "53") (name "Net-(K6A-PA)") (class "Default")
      (node (ref "CON8") (pin "1") (pinfunction "1_1") (pintype "passive"))
      (node (ref "K6") (pin "11A") (pinfunction "PA_11A") (pintype "passive"))
      (node (ref "K6") (pin "11B") (pinfunction "PB_11B") (pintype "passive"))
    )
    (net (code "54") (name "Net-(K6A-SA)") (class "Default")
      (node (ref "CON8") (pin "2") (pinfunction "2_2") (pintype "passive"))
      (node (ref "K6") (pin "14A") (pinfunction "SA_14A") (pintype "passive"))
      (node (ref "K6") (pin "14B") (pinfunction "SB_14B") (pintype "passive"))
    )
    (net (code "55") (name "Net-(K6B-S+)") (class "Default")
      (node (ref "K6") (pin "A1") (pinfunction "S+_A1") (pintype "passive"))
      (node (ref "R19") (pin "2") (pinfunction "2_2") (pintype "passive"))
    )
    (net (code "56") (name "unconnected-(CON1-Pad3)") (class "Default")
      (node (ref "CON1") (pin "3") (pinfunction "3_3") (pintype "passive"))
    )
    (net (code "57") (name "unconnected-(CON1-Pad6)") (class "Default")
      (node (ref "CON1") (pin "6") (pinfunction "6_6") (pintype "passive"))
    )
    (net (code "58") (name "unconnected-(CON2-Pad3)") (class "Default")
      (node (ref "CON2") (pin "3") (pinfunction "3_3") (pintype "passive"))
    )
    (net (code "59") (name "unconnected-(CON2-Pad6)") (class "Default")
      (node (ref "CON2") (pin "6") (pinfunction "6_6") (pintype "passive"))
    )
    (net (code "60") (name "unconnected-(IC1-RA2{slash}AN2-Pad4)") (class "Default")
      (node (ref "IC1") (pin "4") (pinfunction "RA2/AN2_4") (pintype "bidirectional"))
    )
    (net (code "61") (name "unconnected-(IC1-RA3{slash}AN3-Pad5)") (class "Default")
      (node (ref "IC1") (pin "5") (pinfunction "RA3/AN3_5") (pintype "bidirectional"))
    )
    (net (code "62") (name "unconnected-(IC1-RA5{slash}AN4-Pad7)") (class "Default")
      (node (ref "IC1") (pin "7") (pinfunction "RA5/AN4_7") (pintype "bidirectional"))
    )
    (net (code "63") (name "unconnected-(IC1-RB0{slash}AN10{slash}INT0-Pad21)") (class "Default")
      (node (ref "IC1") (pin "21") (pinfunction "RB0/AN10/INT0_21") (pintype "bidirectional"))
    )
    (net (code "64") (name "unconnected-(IC1-RB1{slash}AN8{slash}INT1-Pad22)") (class "Default")
      (node (ref "IC1") (pin "22") (pinfunction "RB1/AN8/INT1_22") (pintype "bidirectional"))
    )
    (net (code "65") (name "unconnected-(IC1-RB4{slash}AN9-Pad25)") (class "Default")
      (node (ref "IC1") (pin "25") (pinfunction "RB4/AN9_25") (pintype "bidirectional"))
    )
    (net (code "66") (name "unconnected-(IC1-RB5{slash}CCP5-Pad26)") (class "Default")
      (node (ref "IC1") (pin "26") (pinfunction "RB5/CCP5_26") (pintype "bidirectional"))
    )
    (net (code "67") (name "unconnected-(IC1-RC6{slash}TX1{slash}CCP3-Pad17)") (class "Default")
      (node (ref "IC1") (pin "17") (pinfunction "RC6/TX1/CCP3_17") (pintype "bidirectional"))
    )
    (net (code "68") (name "unconnected-(IC1-RC7{slash}RX1{slash}CCP4-Pad18)") (class "Default")
      (node (ref "IC1") (pin "18") (pinfunction "RC7/RX1/CCP4_18") (pintype "bidirectional"))
    )
    (net (code "69") (name "unconnected-(IC2-SPLIT-Pad5)") (class "Default")
      (node (ref "IC2") (pin "5") (pinfunction "SPLIT_5") (pintype "bidirectional"))
    )
    (net (code "70") (name "unconnected-(IC5-O7-Pad10)") (class "Default")
      (node (ref "IC5") (pin "10") (pinfunction "O7_10") (pintype "open_collector"))
    )
    (net (code "71") (name "unconnected-(K1A-OA-Pad12A)") (class "Default")
      (node (ref "K1") (pin "12A") (pinfunction "OA_12A") (pintype "passive"))
    )
    (net (code "72") (name "unconnected-(K1A-OB-Pad12B)") (class "Default")
      (node (ref "K1") (pin "12B") (pinfunction "OB_12B") (pintype "passive"))
    )
    (net (code "73") (name "unconnected-(K1B---PadA3)") (class "Default")
      (node (ref "K1") (pin "A3") (pinfunction "-_A3") (pintype "passive"))
    )
    (net (code "74") (name "unconnected-(K2A-OA-Pad12A)") (class "Default")
      (node (ref "K2") (pin "12A") (pinfunction "OA_12A") (pintype "passive"))
    )
    (net (code "75") (name "unconnected-(K2A-OB-Pad12B)") (class "Default")
      (node (ref "K2") (pin "12B") (pinfunction "OB_12B") (pintype "passive"))
    )
    (net (code "76") (name "unconnected-(K2B---PadA3)") (class "Default")
      (node (ref "K2") (pin "A3") (pinfunction "-_A3") (pintype "passive"))
    )
    (net (code "77") (name "unconnected-(K3A-OA-Pad12A)") (class "Default")
      (node (ref "K3") (pin "12A") (pinfunction "OA_12A") (pintype "passive"))
    )
    (net (code "78") (name "unconnected-(K3A-OB-Pad12B)") (class "Default")
      (node (ref "K3") (pin "12B") (pinfunction "OB_12B") (pintype "passive"))
    )
    (net (code "79") (name "unconnected-(K3B---PadA3)") (class "Default")
      (node (ref "K3") (pin "A3") (pinfunction "-_A3") (pintype "passive"))
    )
    (net (code "80") (name "unconnected-(K4A-OA-Pad12A)") (class "Default")
      (node (ref "K4") (pin "12A") (pinfunction "OA_12A") (pintype "passive"))
    )
    (net (code "81") (name "unconnected-(K4A-OB-Pad12B)") (class "Default")
      (node (ref "K4") (pin "12B") (pinfunction "OB_12B") (pintype "passive"))
    )
    (net (code "82") (name "unconnected-(K4B---PadA3)") (class "Default")
      (node (ref "K4") (pin "A3") (pinfunction "-_A3") (pintype "passive"))
    )
    (net (code "83") (name "unconnected-(K5A-OA-Pad12A)") (class "Default")
      (node (ref "K5") (pin "12A") (pinfunction "OA_12A") (pintype "passive"))
    )
    (net (code "84") (name "unconnected-(K5A-OB-Pad12B)") (class "Default")
      (node (ref "K5") (pin "12B") (pinfunction "OB_12B") (pintype "passive"))
    )
    (net (code "85") (name "unconnected-(K5B---PadA3)") (class "Default")
      (node (ref "K5") (pin "A3") (pinfunction "-_A3") (pintype "passive"))
    )
    (net (code "86") (name "unconnected-(K6A-OA-Pad12A)") (class "Default")
      (node (ref "K6") (pin "12A") (pinfunction "OA_12A") (pintype "passive"))
    )
    (net (code "87") (name "unconnected-(K6A-OB-Pad12B)") (class "Default")
      (node (ref "K6") (pin "12B") (pinfunction "OB_12B") (pintype "passive"))
    )
    (net (code "88") (name "unconnected-(K6B---PadA3)") (class "Default")
      (node (ref "K6") (pin "A3") (pinfunction "-_A3") (pintype "passive"))
    )
  )
)
